# M100A.net
KiCad netlist of a schematic drawn in EAGLE
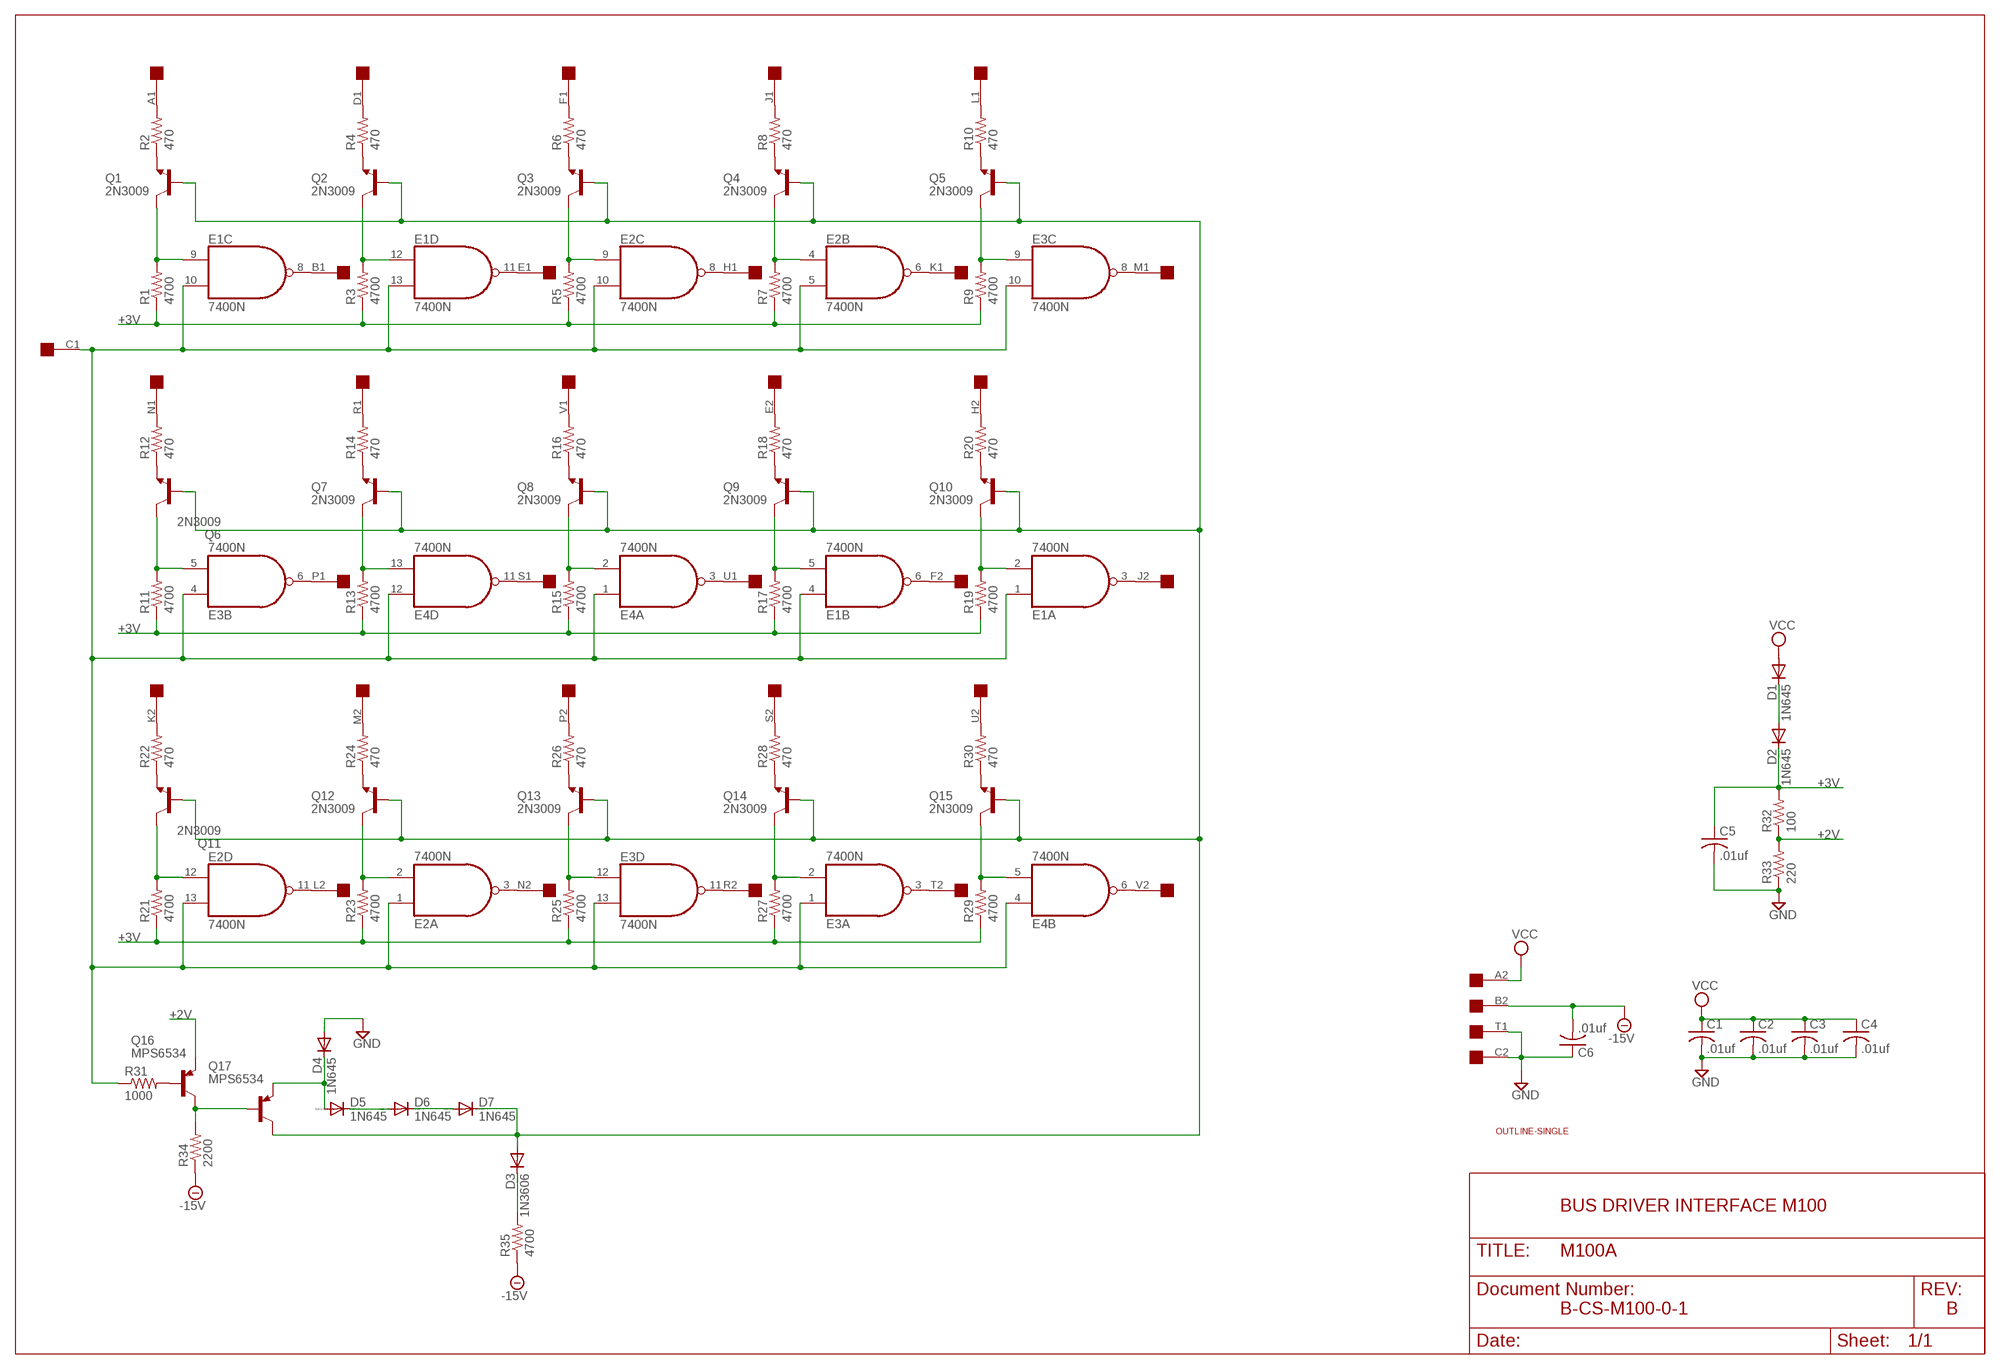
[diagram p0: schematic, sheet 1]

(export (version "E")
  (design (tool "Eeschema 10.0.6"))
  (components
    (comp (ref "C1")
      (value ".01uf")
      (footprint "eagle-import:C050-025X075")
      (libsource (lib "eagle-import") (part "C-US050-025X075"))
    )
    (comp (ref "C2")
      (value ".01uf")
      (footprint "eagle-import:C050-025X075")
      (libsource (lib "eagle-import") (part "C-US050-025X075"))
    )
    (comp (ref "C3")
      (value ".01uf")
      (footprint "eagle-import:C050-025X075")
      (libsource (lib "eagle-import") (part "C-US050-025X075"))
    )
    (comp (ref "C4")
      (value ".01uf")
      (footprint "eagle-import:C050-025X075")
      (libsource (lib "eagle-import") (part "C-US050-025X075"))
    )
    (comp (ref "C5")
      (value ".01uf")
      (footprint "eagle-import:C050-025X075")
      (libsource (lib "eagle-import") (part "C-US050-025X075"))
    )
    (comp (ref "C6")
      (value ".01uf")
      (footprint "eagle-import:C050-025X075")
      (libsource (lib "eagle-import") (part "C-US050-025X075"))
    )
    (comp (ref "D1")
      (value "1N645")
      (footprint "eagle-import:DO35-10")
      (libsource (lib "eagle-import") (part "1N4148DO35-10"))
    )
    (comp (ref "D2")
      (value "1N645")
      (footprint "eagle-import:DO35-10")
      (libsource (lib "eagle-import") (part "1N4148DO35-10"))
    )
    (comp (ref "D3")
      (value "1N3606")
      (footprint "eagle-import:DO35-10")
      (libsource (lib "eagle-import") (part "1N4148DO35-10"))
    )
    (comp (ref "D4")
      (value "1N645")
      (footprint "eagle-import:DO35-10")
      (libsource (lib "eagle-import") (part "1N4148DO35-10"))
    )
    (comp (ref "D5")
      (value "1N645")
      (footprint "eagle-import:DO35-10")
      (libsource (lib "eagle-import") (part "1N4148DO35-10"))
    )
    (comp (ref "D6")
      (value "1N645")
      (footprint "eagle-import:DO35-10")
      (libsource (lib "eagle-import") (part "1N4148DO35-10"))
    )
    (comp (ref "D7")
      (value "1N645")
      (footprint "eagle-import:DO35-10")
      (libsource (lib "eagle-import") (part "1N4148DO35-10"))
    )
    (comp (ref "E1")
      (value "7400N")
      (footprint "eagle-import:DIL14")
      (libsource (lib "eagle-import") (part "7400N"))
    )
    (comp (ref "E2")
      (value "7400N")
      (footprint "eagle-import:DIL14")
      (libsource (lib "eagle-import") (part "7400N"))
    )
    (comp (ref "E3")
      (value "7400N")
      (footprint "eagle-import:DIL14")
      (libsource (lib "eagle-import") (part "7400N"))
    )
    (comp (ref "E4")
      (value "7400N")
      (footprint "eagle-import:DIL14")
      (libsource (lib "eagle-import") (part "7400N"))
    )
    (comp (ref "Q1")
      (value "2N3009")
      (footprint "eagle-import:TO5")
      (libsource (lib "eagle-import") (part "2N2219"))
    )
    (comp (ref "Q2")
      (value "2N3009")
      (footprint "eagle-import:TO5")
      (libsource (lib "eagle-import") (part "2N2219"))
    )
    (comp (ref "Q3")
      (value "2N3009")
      (footprint "eagle-import:TO5")
      (libsource (lib "eagle-import") (part "2N2219"))
    )
    (comp (ref "Q4")
      (value "2N3009")
      (footprint "eagle-import:TO5")
      (libsource (lib "eagle-import") (part "2N2219"))
    )
    (comp (ref "Q5")
      (value "2N3009")
      (footprint "eagle-import:TO5")
      (libsource (lib "eagle-import") (part "2N2219"))
    )
    (comp (ref "Q6")
      (value "2N3009")
      (footprint "eagle-import:TO5")
      (libsource (lib "eagle-import") (part "2N2219"))
    )
    (comp (ref "Q7")
      (value "2N3009")
      (footprint "eagle-import:TO5")
      (libsource (lib "eagle-import") (part "2N2219"))
    )
    (comp (ref "Q8")
      (value "2N3009")
      (footprint "eagle-import:TO5")
      (libsource (lib "eagle-import") (part "2N2219"))
    )
    (comp (ref "Q9")
      (value "2N3009")
      (footprint "eagle-import:TO5")
      (libsource (lib "eagle-import") (part "2N2219"))
    )
    (comp (ref "Q10")
      (value "2N3009")
      (footprint "eagle-import:TO5")
      (libsource (lib "eagle-import") (part "2N2219"))
    )
    (comp (ref "Q11")
      (value "2N3009")
      (footprint "eagle-import:TO5")
      (libsource (lib "eagle-import") (part "2N2219"))
    )
    (comp (ref "Q12")
      (value "2N3009")
      (footprint "eagle-import:TO5")
      (libsource (lib "eagle-import") (part "2N2219"))
    )
    (comp (ref "Q13")
      (value "2N3009")
      (footprint "eagle-import:TO5")
      (libsource (lib "eagle-import") (part "2N2219"))
    )
    (comp (ref "Q14")
      (value "2N3009")
      (footprint "eagle-import:TO5")
      (libsource (lib "eagle-import") (part "2N2219"))
    )
    (comp (ref "Q15")
      (value "2N3009")
      (footprint "eagle-import:TO5")
      (libsource (lib "eagle-import") (part "2N2219"))
    )
    (comp (ref "Q16")
      (value "MPS6534")
      (footprint "eagle-import:TO5")
      (libsource (lib "eagle-import") (part "-PNP-TO5"))
    )
    (comp (ref "Q17")
      (value "MPS6534")
      (footprint "eagle-import:TO5")
      (libsource (lib "eagle-import") (part "-PNP-TO5"))
    )
    (comp (ref "R1")
      (value "4700")
      (footprint "eagle-import:0207_10")
      (libsource (lib "eagle-import") (part "R-US_0207/10"))
    )
    (comp (ref "R2")
      (value "470")
      (footprint "eagle-import:0207_10")
      (libsource (lib "eagle-import") (part "R-US_0207/10"))
    )
    (comp (ref "R3")
      (value "4700")
      (footprint "eagle-import:0207_10")
      (libsource (lib "eagle-import") (part "R-US_0207/10"))
    )
    (comp (ref "R4")
      (value "470")
      (footprint "eagle-import:0207_10")
      (libsource (lib "eagle-import") (part "R-US_0207/10"))
    )
    (comp (ref "R5")
      (value "4700")
      (footprint "eagle-import:0207_10")
      (libsource (lib "eagle-import") (part "R-US_0207/10"))
    )
    (comp (ref "R6")
      (value "470")
      (footprint "eagle-import:0207_10")
      (libsource (lib "eagle-import") (part "R-US_0207/10"))
    )
    (comp (ref "R7")
      (value "4700")
      (footprint "eagle-import:0207_10")
      (libsource (lib "eagle-import") (part "R-US_0207/10"))
    )
    (comp (ref "R8")
      (value "470")
      (footprint "eagle-import:0207_10")
      (libsource (lib "eagle-import") (part "R-US_0207/10"))
    )
    (comp (ref "R9")
      (value "4700")
      (footprint "eagle-import:0207_10")
      (libsource (lib "eagle-import") (part "R-US_0207/10"))
    )
    (comp (ref "R10")
      (value "470")
      (footprint "eagle-import:0207_10")
      (libsource (lib "eagle-import") (part "R-US_0207/10"))
    )
    (comp (ref "R11")
      (value "4700")
      (footprint "eagle-import:0207_10")
      (libsource (lib "eagle-import") (part "R-US_0207/10"))
    )
    (comp (ref "R12")
      (value "470")
      (footprint "eagle-import:0207_10")
      (libsource (lib "eagle-import") (part "R-US_0207/10"))
    )
    (comp (ref "R13")
      (value "4700")
      (footprint "eagle-import:0207_10")
      (libsource (lib "eagle-import") (part "R-US_0207/10"))
    )
    (comp (ref "R14")
      (value "470")
      (footprint "eagle-import:0207_10")
      (libsource (lib "eagle-import") (part "R-US_0207/10"))
    )
    (comp (ref "R15")
      (value "4700")
      (footprint "eagle-import:0207_10")
      (libsource (lib "eagle-import") (part "R-US_0207/10"))
    )
    (comp (ref "R16")
      (value "470")
      (footprint "eagle-import:0207_10")
      (libsource (lib "eagle-import") (part "R-US_0207/10"))
    )
    (comp (ref "R17")
      (value "4700")
      (footprint "eagle-import:0207_10")
      (libsource (lib "eagle-import") (part "R-US_0207/10"))
    )
    (comp (ref "R18")
      (value "470")
      (footprint "eagle-import:0207_10")
      (libsource (lib "eagle-import") (part "R-US_0207/10"))
    )
    (comp (ref "R19")
      (value "4700")
      (footprint "eagle-import:0207_10")
      (libsource (lib "eagle-import") (part "R-US_0207/10"))
    )
    (comp (ref "R20")
      (value "470")
      (footprint "eagle-import:0207_10")
      (libsource (lib "eagle-import") (part "R-US_0207/10"))
    )
    (comp (ref "R21")
      (value "4700")
      (footprint "eagle-import:0207_10")
      (libsource (lib "eagle-import") (part "R-US_0207/10"))
    )
    (comp (ref "R22")
      (value "470")
      (footprint "eagle-import:0207_10")
      (libsource (lib "eagle-import") (part "R-US_0207/10"))
    )
    (comp (ref "R23")
      (value "4700")
      (footprint "eagle-import:0207_10")
      (libsource (lib "eagle-import") (part "R-US_0207/10"))
    )
    (comp (ref "R24")
      (value "470")
      (footprint "eagle-import:0207_10")
      (libsource (lib "eagle-import") (part "R-US_0207/10"))
    )
    (comp (ref "R25")
      (value "4700")
      (footprint "eagle-import:0207_10")
      (libsource (lib "eagle-import") (part "R-US_0207/10"))
    )
    (comp (ref "R26")
      (value "470")
      (footprint "eagle-import:0207_10")
      (libsource (lib "eagle-import") (part "R-US_0207/10"))
    )
    (comp (ref "R27")
      (value "4700")
      (footprint "eagle-import:0207_10")
      (libsource (lib "eagle-import") (part "R-US_0207/10"))
    )
    (comp (ref "R28")
      (value "470")
      (footprint "eagle-import:0207_10")
      (libsource (lib "eagle-import") (part "R-US_0207/10"))
    )
    (comp (ref "R29")
      (value "4700")
      (footprint "eagle-import:0207_10")
      (libsource (lib "eagle-import") (part "R-US_0207/10"))
    )
    (comp (ref "R30")
      (value "470")
      (footprint "eagle-import:0207_10")
      (libsource (lib "eagle-import") (part "R-US_0207/10"))
    )
    (comp (ref "R31")
      (value "1000")
      (footprint "eagle-import:0207_10")
      (libsource (lib "eagle-import") (part "R-US_0207/10"))
    )
    (comp (ref "R32")
      (value "100")
      (footprint "eagle-import:0207_10")
      (libsource (lib "eagle-import") (part "R-US_0207/10"))
    )
    (comp (ref "R33")
      (value "220")
      (footprint "eagle-import:0207_10")
      (libsource (lib "eagle-import") (part "R-US_0207/10"))
    )
    (comp (ref "R34")
      (value "2200")
      (footprint "eagle-import:0207_10")
      (libsource (lib "eagle-import") (part "R-US_0207/10"))
    )
    (comp (ref "R35")
      (value "4700")
      (footprint "eagle-import:0207_10")
      (libsource (lib "eagle-import") (part "R-US_0207/10"))
    )
    (comp (ref "U$1")
      (value "SINGLE")
      (footprint "eagle-import:EDGE-CON2")
      (libsource (lib "eagle-import") (part "SINGLE"))
    )
    (comp (ref "U$2")
      (value "OUTLINE-SINGLE")
      (footprint "eagle-import:SINGLE")
      (libsource (lib "eagle-import") (part "OUTLINE-SINGLE"))
    )
  )
  (nets
    (net (code "1") (name "-15V") (class "Default")
      (node (ref "C6") (pin "2") (pinfunction "2_2") (pintype "passive"))
      (node (ref "R34") (pin "1") (pinfunction "1_1") (pintype "passive"))
      (node (ref "R35") (pin "1") (pinfunction "1_1") (pintype "passive"))
      (node (ref "U$1") (pin "B2") (pinfunction "1_B2") (pintype "bidirectional"))
    )
    (net (code "2") (name "/+2V") (class "Default")
      (node (ref "Q16") (pin "1") (pinfunction "E_1") (pintype "passive"))
      (node (ref "R32") (pin "1") (pinfunction "1_1") (pintype "passive"))
      (node (ref "R33") (pin "2") (pinfunction "2_2") (pintype "passive"))
    )
    (net (code "3") (name "/+3V") (class "Default")
      (node (ref "C5") (pin "1") (pinfunction "1_1") (pintype "passive"))
      (node (ref "D2") (pin "C") (pinfunction "C_C") (pintype "passive"))
      (node (ref "R1") (pin "1") (pinfunction "1_1") (pintype "passive"))
      (node (ref "R11") (pin "1") (pinfunction "1_1") (pintype "passive"))
      (node (ref "R13") (pin "1") (pinfunction "1_1") (pintype "passive"))
      (node (ref "R15") (pin "1") (pinfunction "1_1") (pintype "passive"))
      (node (ref "R17") (pin "1") (pinfunction "1_1") (pintype "passive"))
      (node (ref "R19") (pin "1") (pinfunction "1_1") (pintype "passive"))
      (node (ref "R21") (pin "1") (pinfunction "1_1") (pintype "passive"))
      (node (ref "R23") (pin "1") (pinfunction "1_1") (pintype "passive"))
      (node (ref "R25") (pin "1") (pinfunction "1_1") (pintype "passive"))
      (node (ref "R27") (pin "1") (pinfunction "1_1") (pintype "passive"))
      (node (ref "R29") (pin "1") (pinfunction "1_1") (pintype "passive"))
      (node (ref "R3") (pin "1") (pinfunction "1_1") (pintype "passive"))
      (node (ref "R32") (pin "2") (pinfunction "2_2") (pintype "passive"))
      (node (ref "R5") (pin "1") (pinfunction "1_1") (pintype "passive"))
      (node (ref "R7") (pin "1") (pinfunction "1_1") (pintype "passive"))
      (node (ref "R9") (pin "1") (pinfunction "1_1") (pintype "passive"))
    )
    (net (code "4") (name "GND") (class "Default")
      (node (ref "C1") (pin "2") (pinfunction "2_2") (pintype "passive"))
      (node (ref "C2") (pin "2") (pinfunction "2_2") (pintype "passive"))
      (node (ref "C3") (pin "2") (pinfunction "2_2") (pintype "passive"))
      (node (ref "C4") (pin "2") (pinfunction "2_2") (pintype "passive"))
      (node (ref "C5") (pin "2") (pinfunction "2_2") (pintype "passive"))
      (node (ref "C6") (pin "1") (pinfunction "1_1") (pintype "passive"))
      (node (ref "D4") (pin "A") (pinfunction "A_A") (pintype "passive"))
      (node (ref "R33") (pin "1") (pinfunction "1_1") (pintype "passive"))
      (node (ref "U$1") (pin "C2") (pinfunction "1_C2") (pintype "bidirectional"))
      (node (ref "U$1") (pin "T1") (pinfunction "1_T1") (pintype "bidirectional"))
    )
    (net (code "5") (name "Net-(D1-PadC)") (class "Default")
      (node (ref "D1") (pin "C") (pinfunction "C_C") (pintype "passive"))
      (node (ref "D2") (pin "A") (pinfunction "A_A") (pintype "passive"))
    )
    (net (code "6") (name "Net-(D3-PadC)") (class "Default")
      (node (ref "D3") (pin "C") (pinfunction "C_C") (pintype "passive"))
      (node (ref "R35") (pin "2") (pinfunction "2_2") (pintype "passive"))
    )
    (net (code "7") (name "Net-(D5-PadC)") (class "Default")
      (node (ref "D5") (pin "C") (pinfunction "C_C") (pintype "passive"))
      (node (ref "D6") (pin "A") (pinfunction "A_A") (pintype "passive"))
    )
    (net (code "8") (name "Net-(D6-PadC)") (class "Default")
      (node (ref "D6") (pin "C") (pinfunction "C_C") (pintype "passive"))
      (node (ref "D7") (pin "A") (pinfunction "A_A") (pintype "passive"))
    )
    (net (code "9") (name "Net-(E1A-I0)") (class "Default")
      (node (ref "E1") (pin "1") (pinfunction "I0_1") (pintype "input"))
      (node (ref "E1") (pin "10") (pinfunction "I1_10") (pintype "input"))
      (node (ref "E1") (pin "13") (pinfunction "I1_13") (pintype "input"))
      (node (ref "E1") (pin "4") (pinfunction "I0_4") (pintype "input"))
      (node (ref "E2") (pin "1") (pinfunction "I0_1") (pintype "input"))
      (node (ref "E2") (pin "10") (pinfunction "I1_10") (pintype "input"))
      (node (ref "E2") (pin "13") (pinfunction "I1_13") (pintype "input"))
      (node (ref "E2") (pin "5") (pinfunction "I1_5") (pintype "input"))
      (node (ref "E3") (pin "1") (pinfunction "I0_1") (pintype "input"))
      (node (ref "E3") (pin "10") (pinfunction "I1_10") (pintype "input"))
      (node (ref "E3") (pin "13") (pinfunction "I1_13") (pintype "input"))
      (node (ref "E3") (pin "4") (pinfunction "I0_4") (pintype "input"))
      (node (ref "E4") (pin "1") (pinfunction "I0_1") (pintype "input"))
      (node (ref "E4") (pin "12") (pinfunction "I0_12") (pintype "input"))
      (node (ref "E4") (pin "4") (pinfunction "I0_4") (pintype "input"))
      (node (ref "R31") (pin "1") (pinfunction "1_1") (pintype "passive"))
      (node (ref "U$1") (pin "C1") (pinfunction "1_C1") (pintype "bidirectional"))
    )
    (net (code "10") (name "Net-(E1A-I1)") (class "Default")
      (node (ref "E1") (pin "2") (pinfunction "I1_2") (pintype "input"))
      (node (ref "Q10") (pin "3") (pinfunction "C_3") (pintype "passive"))
      (node (ref "R19") (pin "2") (pinfunction "2_2") (pintype "passive"))
    )
    (net (code "11") (name "Net-(E1A-O)") (class "Default")
      (node (ref "E1") (pin "3") (pinfunction "O_3") (pintype "output"))
      (node (ref "U$1") (pin "J2") (pinfunction "1_J2") (pintype "bidirectional"))
    )
    (net (code "12") (name "Net-(E1B-I1)") (class "Default")
      (node (ref "E1") (pin "5") (pinfunction "I1_5") (pintype "input"))
      (node (ref "Q9") (pin "3") (pinfunction "C_3") (pintype "passive"))
      (node (ref "R17") (pin "2") (pinfunction "2_2") (pintype "passive"))
    )
    (net (code "13") (name "Net-(E1B-O)") (class "Default")
      (node (ref "E1") (pin "6") (pinfunction "O_6") (pintype "output"))
      (node (ref "U$1") (pin "F2") (pinfunction "1_F2") (pintype "bidirectional"))
    )
    (net (code "14") (name "Net-(E1C-I0)") (class "Default")
      (node (ref "E1") (pin "9") (pinfunction "I0_9") (pintype "input"))
      (node (ref "Q1") (pin "3") (pinfunction "C_3") (pintype "passive"))
      (node (ref "R1") (pin "2") (pinfunction "2_2") (pintype "passive"))
    )
    (net (code "15") (name "Net-(E1C-O)") (class "Default")
      (node (ref "E1") (pin "8") (pinfunction "O_8") (pintype "output"))
      (node (ref "U$1") (pin "B1") (pinfunction "1_B1") (pintype "bidirectional"))
    )
    (net (code "16") (name "Net-(E1D-I0)") (class "Default")
      (node (ref "E1") (pin "12") (pinfunction "I0_12") (pintype "input"))
      (node (ref "Q2") (pin "3") (pinfunction "C_3") (pintype "passive"))
      (node (ref "R3") (pin "2") (pinfunction "2_2") (pintype "passive"))
    )
    (net (code "17") (name "Net-(E1D-O)") (class "Default")
      (node (ref "E1") (pin "11") (pinfunction "O_11") (pintype "output"))
      (node (ref "U$1") (pin "E1") (pinfunction "1_E1") (pintype "bidirectional"))
    )
    (net (code "18") (name "Net-(E2A-I1)") (class "Default")
      (node (ref "E2") (pin "2") (pinfunction "I1_2") (pintype "input"))
      (node (ref "Q12") (pin "3") (pinfunction "C_3") (pintype "passive"))
      (node (ref "R23") (pin "2") (pinfunction "2_2") (pintype "passive"))
    )
    (net (code "19") (name "Net-(E2A-O)") (class "Default")
      (node (ref "E2") (pin "3") (pinfunction "O_3") (pintype "output"))
      (node (ref "U$1") (pin "N2") (pinfunction "1_N2") (pintype "bidirectional"))
    )
    (net (code "20") (name "Net-(E2B-I0)") (class "Default")
      (node (ref "E2") (pin "4") (pinfunction "I0_4") (pintype "input"))
      (node (ref "Q4") (pin "3") (pinfunction "C_3") (pintype "passive"))
      (node (ref "R7") (pin "2") (pinfunction "2_2") (pintype "passive"))
    )
    (net (code "21") (name "Net-(E2B-O)") (class "Default")
      (node (ref "E2") (pin "6") (pinfunction "O_6") (pintype "output"))
      (node (ref "U$1") (pin "K1") (pinfunction "1_K1") (pintype "bidirectional"))
    )
    (net (code "22") (name "Net-(E2C-I0)") (class "Default")
      (node (ref "E2") (pin "9") (pinfunction "I0_9") (pintype "input"))
      (node (ref "Q3") (pin "3") (pinfunction "C_3") (pintype "passive"))
      (node (ref "R5") (pin "2") (pinfunction "2_2") (pintype "passive"))
    )
    (net (code "23") (name "Net-(E2C-O)") (class "Default")
      (node (ref "E2") (pin "8") (pinfunction "O_8") (pintype "output"))
      (node (ref "U$1") (pin "H1") (pinfunction "1_H1") (pintype "bidirectional"))
    )
    (net (code "24") (name "Net-(E2D-I0)") (class "Default")
      (node (ref "E2") (pin "12") (pinfunction "I0_12") (pintype "input"))
      (node (ref "Q11") (pin "3") (pinfunction "C_3") (pintype "passive"))
      (node (ref "R21") (pin "2") (pinfunction "2_2") (pintype "passive"))
    )
    (net (code "25") (name "Net-(E2D-O)") (class "Default")
      (node (ref "E2") (pin "11") (pinfunction "O_11") (pintype "output"))
      (node (ref "U$1") (pin "L2") (pinfunction "1_L2") (pintype "bidirectional"))
    )
    (net (code "26") (name "Net-(E3A-I1)") (class "Default")
      (node (ref "E3") (pin "2") (pinfunction "I1_2") (pintype "input"))
      (node (ref "Q14") (pin "3") (pinfunction "C_3") (pintype "passive"))
      (node (ref "R27") (pin "2") (pinfunction "2_2") (pintype "passive"))
    )
    (net (code "27") (name "Net-(E3A-O)") (class "Default")
      (node (ref "E3") (pin "3") (pinfunction "O_3") (pintype "output"))
      (node (ref "U$1") (pin "T2") (pinfunction "1_T2") (pintype "bidirectional"))
    )
    (net (code "28") (name "Net-(E3B-I1)") (class "Default")
      (node (ref "E3") (pin "5") (pinfunction "I1_5") (pintype "input"))
      (node (ref "Q6") (pin "3") (pinfunction "C_3") (pintype "passive"))
      (node (ref "R11") (pin "2") (pinfunction "2_2") (pintype "passive"))
    )
    (net (code "29") (name "Net-(E3B-O)") (class "Default")
      (node (ref "E3") (pin "6") (pinfunction "O_6") (pintype "output"))
      (node (ref "U$1") (pin "P1") (pinfunction "1_P1") (pintype "bidirectional"))
    )
    (net (code "30") (name "Net-(E3C-I0)") (class "Default")
      (node (ref "E3") (pin "9") (pinfunction "I0_9") (pintype "input"))
      (node (ref "Q5") (pin "3") (pinfunction "C_3") (pintype "passive"))
      (node (ref "R9") (pin "2") (pinfunction "2_2") (pintype "passive"))
    )
    (net (code "31") (name "Net-(E3C-O)") (class "Default")
      (node (ref "E3") (pin "8") (pinfunction "O_8") (pintype "output"))
      (node (ref "U$1") (pin "M1") (pinfunction "1_M1") (pintype "bidirectional"))
    )
    (net (code "32") (name "Net-(E3D-I0)") (class "Default")
      (node (ref "E3") (pin "12") (pinfunction "I0_12") (pintype "input"))
      (node (ref "Q13") (pin "3") (pinfunction "C_3") (pintype "passive"))
      (node (ref "R25") (pin "2") (pinfunction "2_2") (pintype "passive"))
    )
    (net (code "33") (name "Net-(E3D-O)") (class "Default")
      (node (ref "E3") (pin "11") (pinfunction "O_11") (pintype "output"))
      (node (ref "U$1") (pin "R2") (pinfunction "1_R2") (pintype "bidirectional"))
    )
    (net (code "34") (name "Net-(E4A-I1)") (class "Default")
      (node (ref "E4") (pin "2") (pinfunction "I1_2") (pintype "input"))
      (node (ref "Q8") (pin "3") (pinfunction "C_3") (pintype "passive"))
      (node (ref "R15") (pin "2") (pinfunction "2_2") (pintype "passive"))
    )
    (net (code "35") (name "Net-(E4A-O)") (class "Default")
      (node (ref "E4") (pin "3") (pinfunction "O_3") (pintype "output"))
      (node (ref "U$1") (pin "U1") (pinfunction "1_U1") (pintype "bidirectional"))
    )
    (net (code "36") (name "Net-(E4B-I1)") (class "Default")
      (node (ref "E4") (pin "5") (pinfunction "I1_5") (pintype "input"))
      (node (ref "Q15") (pin "3") (pinfunction "C_3") (pintype "passive"))
      (node (ref "R29") (pin "2") (pinfunction "2_2") (pintype "passive"))
    )
    (net (code "37") (name "Net-(E4B-O)") (class "Default")
      (node (ref "E4") (pin "6") (pinfunction "O_6") (pintype "output"))
      (node (ref "U$1") (pin "V2") (pinfunction "1_V2") (pintype "bidirectional"))
    )
    (net (code "38") (name "Net-(E4D-I1)") (class "Default")
      (node (ref "E4") (pin "13") (pinfunction "I1_13") (pintype "input"))
      (node (ref "Q7") (pin "3") (pinfunction "C_3") (pintype "passive"))
      (node (ref "R13") (pin "2") (pinfunction "2_2") (pintype "passive"))
    )
    (net (code "39") (name "Net-(E4D-O)") (class "Default")
      (node (ref "E4") (pin "11") (pinfunction "O_11") (pintype "output"))
      (node (ref "U$1") (pin "S1") (pinfunction "1_S1") (pintype "bidirectional"))
    )
    (net (code "40") (name "Net-(Q1-B)") (class "Default")
      (node (ref "D3") (pin "A") (pinfunction "A_A") (pintype "passive"))
      (node (ref "D7") (pin "C") (pinfunction "C_C") (pintype "passive"))
      (node (ref "Q1") (pin "2") (pinfunction "B_2") (pintype "passive"))
      (node (ref "Q10") (pin "2") (pinfunction "B_2") (pintype "passive"))
      (node (ref "Q11") (pin "2") (pinfunction "B_2") (pintype "passive"))
      (node (ref "Q12") (pin "2") (pinfunction "B_2") (pintype "passive"))
      (node (ref "Q13") (pin "2") (pinfunction "B_2") (pintype "passive"))
      (node (ref "Q14") (pin "2") (pinfunction "B_2") (pintype "passive"))
      (node (ref "Q15") (pin "2") (pinfunction "B_2") (pintype "passive"))
      (node (ref "Q17") (pin "3") (pinfunction "C_3") (pintype "passive"))
      (node (ref "Q2") (pin "2") (pinfunction "B_2") (pintype "passive"))
      (node (ref "Q3") (pin "2") (pinfunction "B_2") (pintype "passive"))
      (node (ref "Q4") (pin "2") (pinfunction "B_2") (pintype "passive"))
      (node (ref "Q5") (pin "2") (pinfunction "B_2") (pintype "passive"))
      (node (ref "Q6") (pin "2") (pinfunction "B_2") (pintype "passive"))
      (node (ref "Q7") (pin "2") (pinfunction "B_2") (pintype "passive"))
      (node (ref "Q8") (pin "2") (pinfunction "B_2") (pintype "passive"))
      (node (ref "Q9") (pin "2") (pinfunction "B_2") (pintype "passive"))
    )
    (net (code "41") (name "Net-(Q1-E)") (class "Default")
      (node (ref "Q1") (pin "1") (pinfunction "E_1") (pintype "passive"))
      (node (ref "R2") (pin "1") (pinfunction "1_1") (pintype "passive"))
    )
    (net (code "42") (name "Net-(Q2-E)") (class "Default")
      (node (ref "Q2") (pin "1") (pinfunction "E_1") (pintype "passive"))
      (node (ref "R4") (pin "1") (pinfunction "1_1") (pintype "passive"))
    )
    (net (code "43") (name "Net-(Q3-E)") (class "Default")
      (node (ref "Q3") (pin "1") (pinfunction "E_1") (pintype "passive"))
      (node (ref "R6") (pin "1") (pinfunction "1_1") (pintype "passive"))
    )
    (net (code "44") (name "Net-(Q4-E)") (class "Default")
      (node (ref "Q4") (pin "1") (pinfunction "E_1") (pintype "passive"))
      (node (ref "R8") (pin "1") (pinfunction "1_1") (pintype "passive"))
    )
    (net (code "45") (name "Net-(Q5-E)") (class "Default")
      (node (ref "Q5") (pin "1") (pinfunction "E_1") (pintype "passive"))
      (node (ref "R10") (pin "1") (pinfunction "1_1") (pintype "passive"))
    )
    (net (code "46") (name "Net-(Q6-E)") (class "Default")
      (node (ref "Q6") (pin "1") (pinfunction "E_1") (pintype "passive"))
      (node (ref "R12") (pin "1") (pinfunction "1_1") (pintype "passive"))
    )
    (net (code "47") (name "Net-(Q7-E)") (class "Default")
      (node (ref "Q7") (pin "1") (pinfunction "E_1") (pintype "passive"))
      (node (ref "R14") (pin "1") (pinfunction "1_1") (pintype "passive"))
    )
    (net (code "48") (name "Net-(Q8-E)") (class "Default")
      (node (ref "Q8") (pin "1") (pinfunction "E_1") (pintype "passive"))
      (node (ref "R16") (pin "1") (pinfunction "1_1") (pintype "passive"))
    )
    (net (code "49") (name "Net-(Q9-E)") (class "Default")
      (node (ref "Q9") (pin "1") (pinfunction "E_1") (pintype "passive"))
      (node (ref "R18") (pin "1") (pinfunction "1_1") (pintype "passive"))
    )
    (net (code "50") (name "Net-(Q10-E)") (class "Default")
      (node (ref "Q10") (pin "1") (pinfunction "E_1") (pintype "passive"))
      (node (ref "R20") (pin "1") (pinfunction "1_1") (pintype "passive"))
    )
    (net (code "51") (name "Net-(Q11-E)") (class "Default")
      (node (ref "Q11") (pin "1") (pinfunction "E_1") (pintype "passive"))
      (node (ref "R22") (pin "1") (pinfunction "1_1") (pintype "passive"))
    )
    (net (code "52") (name "Net-(Q12-E)") (class "Default")
      (node (ref "Q12") (pin "1") (pinfunction "E_1") (pintype "passive"))
      (node (ref "R24") (pin "1") (pinfunction "1_1") (pintype "passive"))
    )
    (net (code "53") (name "Net-(Q13-E)") (class "Default")
      (node (ref "Q13") (pin "1") (pinfunction "E_1") (pintype "passive"))
      (node (ref "R26") (pin "1") (pinfunction "1_1") (pintype "passive"))
    )
    (net (code "54") (name "Net-(Q14-E)") (class "Default")
      (node (ref "Q14") (pin "1") (pinfunction "E_1") (pintype "passive"))
      (node (ref "R28") (pin "1") (pinfunction "1_1") (pintype "passive"))
    )
    (net (code "55") (name "Net-(Q15-E)") (class "Default")
      (node (ref "Q15") (pin "1") (pinfunction "E_1") (pintype "passive"))
      (node (ref "R30") (pin "1") (pinfunction "1_1") (pintype "passive"))
    )
    (net (code "56") (name "Net-(Q16-B)") (class "Default")
      (node (ref "Q16") (pin "2") (pinfunction "B_2") (pintype "passive"))
      (node (ref "R31") (pin "2") (pinfunction "2_2") (pintype "passive"))
    )
    (net (code "57") (name "Net-(Q16-C)") (class "Default")
      (node (ref "Q16") (pin "3") (pinfunction "C_3") (pintype "passive"))
      (node (ref "Q17") (pin "2") (pinfunction "B_2") (pintype "passive"))
      (node (ref "R34") (pin "2") (pinfunction "2_2") (pintype "passive"))
    )
    (net (code "58") (name "Net-(Q17-E)") (class "Default")
      (node (ref "D4") (pin "C") (pinfunction "C_C") (pintype "passive"))
      (node (ref "D5") (pin "A") (pinfunction "A_A") (pintype "passive"))
      (node (ref "Q17") (pin "1") (pinfunction "E_1") (pintype "passive"))
    )
    (net (code "59") (name "Net-(U$1A-1)") (class "Default")
      (node (ref "R2") (pin "2") (pinfunction "2_2") (pintype "passive"))
      (node (ref "U$1") (pin "A1") (pinfunction "1_A1") (pintype "bidirectional"))
    )
    (net (code "60") (name "Net-(U$1AA-1)") (class "Default")
      (node (ref "R14") (pin "2") (pinfunction "2_2") (pintype "passive"))
      (node (ref "U$1") (pin "R1") (pinfunction "1_R1") (pintype "bidirectional"))
    )
    (net (code "61") (name "Net-(U$1AD-1)") (class "Default")
      (node (ref "R28") (pin "2") (pinfunction "2_2") (pintype "passive"))
      (node (ref "U$1") (pin "S2") (pinfunction "1_S2") (pintype "bidirectional"))
    )
    (net (code "62") (name "Net-(U$1AH-1)") (class "Default")
      (node (ref "R30") (pin "2") (pinfunction "2_2") (pintype "passive"))
      (node (ref "U$1") (pin "U2") (pinfunction "1_U2") (pintype "bidirectional"))
    )
    (net (code "63") (name "Net-(U$1AI-1)") (class "Default")
      (node (ref "R16") (pin "2") (pinfunction "2_2") (pintype "passive"))
      (node (ref "U$1") (pin "V1") (pinfunction "1_V1") (pintype "bidirectional"))
    )
    (net (code "64") (name "Net-(U$1G-1)") (class "Default")
      (node (ref "R4") (pin "2") (pinfunction "2_2") (pintype "passive"))
      (node (ref "U$1") (pin "D1") (pinfunction "1_D1") (pintype "bidirectional"))
    )
    (net (code "65") (name "Net-(U$1J-1)") (class "Default")
      (node (ref "R18") (pin "2") (pinfunction "2_2") (pintype "passive"))
      (node (ref "U$1") (pin "E2") (pinfunction "1_E2") (pintype "bidirectional"))
    )
    (net (code "66") (name "Net-(U$1K-1)") (class "Default")
      (node (ref "R6") (pin "2") (pinfunction "2_2") (pintype "passive"))
      (node (ref "U$1") (pin "F1") (pinfunction "1_F1") (pintype "bidirectional"))
    )
    (net (code "67") (name "Net-(U$1N-1)") (class "Default")
      (node (ref "R20") (pin "2") (pinfunction "2_2") (pintype "passive"))
      (node (ref "U$1") (pin "H2") (pinfunction "1_H2") (pintype "bidirectional"))
    )
    (net (code "68") (name "Net-(U$1O-1)") (class "Default")
      (node (ref "R8") (pin "2") (pinfunction "2_2") (pintype "passive"))
      (node (ref "U$1") (pin "J1") (pinfunction "1_J1") (pintype "bidirectional"))
    )
    (net (code "69") (name "Net-(U$1R-1)") (class "Default")
      (node (ref "R22") (pin "2") (pinfunction "2_2") (pintype "passive"))
      (node (ref "U$1") (pin "K2") (pinfunction "1_K2") (pintype "bidirectional"))
    )
    (net (code "70") (name "Net-(U$1S-1)") (class "Default")
      (node (ref "R10") (pin "2") (pinfunction "2_2") (pintype "passive"))
      (node (ref "U$1") (pin "L1") (pinfunction "1_L1") (pintype "bidirectional"))
    )
    (net (code "71") (name "Net-(U$1V-1)") (class "Default")
      (node (ref "R24") (pin "2") (pinfunction "2_2") (pintype "passive"))
      (node (ref "U$1") (pin "M2") (pinfunction "1_M2") (pintype "bidirectional"))
    )
    (net (code "72") (name "Net-(U$1W-1)") (class "Default")
      (node (ref "R12") (pin "2") (pinfunction "2_2") (pintype "passive"))
      (node (ref "U$1") (pin "N1") (pinfunction "1_N1") (pintype "bidirectional"))
    )
    (net (code "73") (name "Net-(U$1Z-1)") (class "Default")
      (node (ref "R26") (pin "2") (pinfunction "2_2") (pintype "passive"))
      (node (ref "U$1") (pin "P2") (pinfunction "1_P2") (pintype "bidirectional"))
    )
    (net (code "74") (name "VCC") (class "Default")
      (node (ref "C1") (pin "1") (pinfunction "1_1") (pintype "passive"))
      (node (ref "C2") (pin "1") (pinfunction "1_1") (pintype "passive"))
      (node (ref "C3") (pin "1") (pinfunction "1_1") (pintype "passive"))
      (node (ref "C4") (pin "1") (pinfunction "1_1") (pintype "passive"))
      (node (ref "D1") (pin "A") (pinfunction "A_A") (pintype "passive"))
      (node (ref "U$1") (pin "A2") (pinfunction "1_A2") (pintype "bidirectional"))
    )
  )
)
